# AM-Crystal-RX.net
KiCad netlist of a schematic drawn in EAGLE
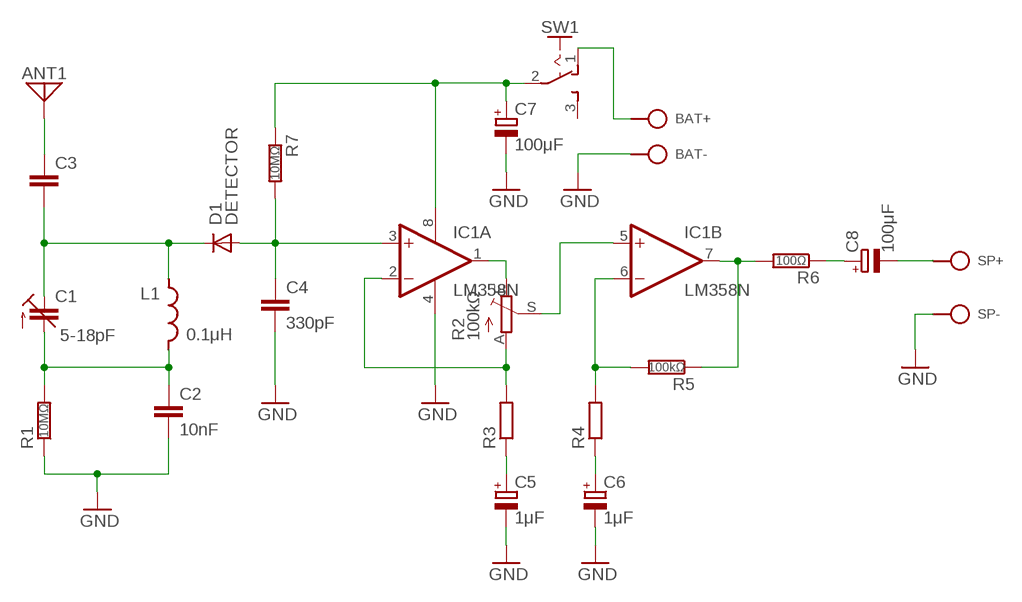
[diagram p0: schematic, sheet 1]

(export (version "E")
  (design (tool "Eeschema 10.0.6"))
  (components
    (comp (ref "ANT1")
      (value "ANT")
      (footprint "eagle-import:SPAD")
      (libsource (lib "eagle-import") (part "ANT"))
    )
    (comp (ref "BAT+")
      (value "BAT+")
      (footprint "eagle-import:SPAD")
      (libsource (lib "eagle-import") (part "SPAD"))
    )
    (comp (ref "BAT-")
      (value "BAT-")
      (footprint "eagle-import:SPAD")
      (libsource (lib "eagle-import") (part "SPAD"))
    )
    (comp (ref "C1")
      (value "5-18pF")
      (footprint "eagle-import:TRIM-2222-808")
      (libsource (lib "eagle-import") (part "C-TR-PH201272222-808-2PIN"))
    )
    (comp (ref "C2")
      (value "10nF")
      (footprint "eagle-import:C050-025X075")
      (libsource (lib "eagle-import") (part "C050-025X075"))
    )
    (comp (ref "C3")
      (value "C025-015X024")
      (footprint "eagle-import:C025-015X024")
      (libsource (lib "eagle-import") (part "C025-015X024"))
    )
    (comp (ref "C4")
      (value "330pF")
      (footprint "eagle-import:C050-024X044")
      (libsource (lib "eagle-import") (part "C050-024X044"))
    )
    (comp (ref "C5")
      (value "1μF")
      (footprint "eagle-import:E2,5-3")
      (libsource (lib "eagle-import") (part "CPOLE2,5-3"))
    )
    (comp (ref "C6")
      (value "1μF")
      (footprint "eagle-import:E2,5-3")
      (libsource (lib "eagle-import") (part "CPOLE2,5-3"))
    )
    (comp (ref "C7")
      (value "100μF")
      (footprint "eagle-import:E2,5-5")
      (libsource (lib "eagle-import") (part "CPOLE2.5-5"))
    )
    (comp (ref "C8")
      (value "100μF")
      (footprint "eagle-import:E2,5-5")
      (libsource (lib "eagle-import") (part "CPOLE2.5-5"))
    )
    (comp (ref "D1")
      (value "DETECTOR")
      (footprint "eagle-import:DO34-10")
      (libsource (lib "eagle-import") (part "1N414834-10"))
    )
    (comp (ref "IC1")
      (value "LM358N")
      (footprint "eagle-import:DIL08")
      (libsource (lib "eagle-import") (part "LM358N"))
    )
    (comp (ref "L1")
      (value "0.1μH")
      (footprint "eagle-import:L-04_10")
      (libsource (lib "eagle-import") (part "L-SHORT04/10"))
    )
    (comp (ref "R1")
      (value "10MΩ")
      (footprint "eagle-import:0202_7-V")
      (libsource (lib "eagle-import") (part "R0202/7-V"))
    )
    (comp (ref "R2")
      (value "100kΩ")
      (footprint "eagle-import:B64Y")
      (libsource (lib "eagle-import") (part "TRIM_EU-B64Y"))
    )
    (comp (ref "R3")
      (value "R0202/7")
      (footprint "eagle-import:0202_7")
      (libsource (lib "eagle-import") (part "R0202/7"))
    )
    (comp (ref "R4")
      (value "R0202/7")
      (footprint "eagle-import:0202_7")
      (libsource (lib "eagle-import") (part "R0202/7"))
    )
    (comp (ref "R5")
      (value "100kΩ")
      (footprint "eagle-import:0202_7")
      (libsource (lib "eagle-import") (part "R0202/7"))
    )
    (comp (ref "R6")
      (value "100Ω")
      (footprint "eagle-import:0202_7")
      (libsource (lib "eagle-import") (part "R0202/7"))
    )
    (comp (ref "R7")
      (value "10MΩ")
      (footprint "eagle-import:0202_7")
      (libsource (lib "eagle-import") (part "R0202/7"))
    )
    (comp (ref "SP+")
      (value "SPKR+")
      (footprint "eagle-import:SPAD")
      (libsource (lib "eagle-import") (part "SPAD"))
    )
    (comp (ref "SP-")
      (value "SPKR-")
      (footprint "eagle-import:SPAD")
      (libsource (lib "eagle-import") (part "SPAD"))
    )
    (comp (ref "SW1")
      (value "SL-SW-1P-2T-H")
      (footprint "eagle-import:SLSW-1P2T-H")
      (libsource (lib "eagle-import") (part "SL-SW-1P-2T-H"))
    )
  )
  (nets
    (net (code "1") (name "GND") (class "Default")
      (node (ref "BAT-") (pin "1") (pinfunction "P$1_1") (pintype "bidirectional"))
      (node (ref "C2") (pin "2") (pinfunction "2_2") (pintype "passive"))
      (node (ref "C4") (pin "2") (pinfunction "2_2") (pintype "passive"))
      (node (ref "C5") (pin "-") (pinfunction "-_-") (pintype "passive"))
      (node (ref "C6") (pin "-") (pinfunction "-_-") (pintype "passive"))
      (node (ref "C7") (pin "-") (pinfunction "-_-") (pintype "passive"))
      (node (ref "IC1") (pin "4") (pinfunction "V-_4") (pintype "power_in"))
      (node (ref "R1") (pin "1") (pinfunction "1_1") (pintype "passive"))
      (node (ref "SP-") (pin "1") (pinfunction "P$1_1") (pintype "bidirectional"))
    )
    (net (code "2") (name "Net-(ANT1-Pad1)") (class "Default")
      (node (ref "ANT1") (pin "1") (pinfunction "1_1") (pintype "output"))
      (node (ref "C3") (pin "1") (pinfunction "1_1") (pintype "passive"))
    )
    (net (code "3") (name "Net-(BAT+-P$1)") (class "Default")
      (node (ref "BAT+") (pin "1") (pinfunction "P$1_1") (pintype "bidirectional"))
      (node (ref "SW1") (pin "1") (pinfunction "O_1") (pintype "passive"))
    )
    (net (code "4") (name "Net-(C1-A)") (class "Default")
      (node (ref "C1") (pin "1") (pinfunction "A_1") (pintype "passive"))
      (node (ref "C3") (pin "2") (pinfunction "2_2") (pintype "passive"))
      (node (ref "D1") (pin "C") (pinfunction "C_C") (pintype "passive"))
      (node (ref "L1") (pin "1") (pinfunction "1_1") (pintype "passive"))
    )
    (net (code "5") (name "Net-(C1-E)") (class "Default")
      (node (ref "C1") (pin "2") (pinfunction "E_2") (pintype "passive"))
      (node (ref "C2") (pin "1") (pinfunction "1_1") (pintype "passive"))
      (node (ref "L1") (pin "2") (pinfunction "2_2") (pintype "passive"))
      (node (ref "R1") (pin "2") (pinfunction "2_2") (pintype "passive"))
    )
    (net (code "6") (name "Net-(C5-Pad+)") (class "Default")
      (node (ref "C5") (pin "+") (pinfunction "+_+") (pintype "passive"))
      (node (ref "R3") (pin "1") (pinfunction "1_1") (pintype "passive"))
    )
    (net (code "7") (name "Net-(C6-Pad+)") (class "Default")
      (node (ref "C6") (pin "+") (pinfunction "+_+") (pintype "passive"))
      (node (ref "R4") (pin "1") (pinfunction "1_1") (pintype "passive"))
    )
    (net (code "8") (name "Net-(C8-Pad+)") (class "Default")
      (node (ref "C8") (pin "+") (pinfunction "+_+") (pintype "passive"))
      (node (ref "R6") (pin "1") (pinfunction "1_1") (pintype "passive"))
    )
    (net (code "9") (name "Net-(IC1A-+IN)") (class "Default")
      (node (ref "C4") (pin "1") (pinfunction "1_1") (pintype "passive"))
      (node (ref "D1") (pin "A") (pinfunction "A_A") (pintype "passive"))
      (node (ref "IC1") (pin "3") (pinfunction "+IN_3") (pintype "input"))
      (node (ref "R7") (pin "2") (pinfunction "2_2") (pintype "passive"))
    )
    (net (code "10") (name "Net-(IC1A--IN)") (class "Default")
      (node (ref "IC1") (pin "2") (pinfunction "-IN_2") (pintype "input"))
      (node (ref "R2") (pin "A") (pinfunction "A_A") (pintype "passive"))
      (node (ref "R3") (pin "2") (pinfunction "2_2") (pintype "passive"))
    )
    (net (code "11") (name "Net-(IC1A-OUT)") (class "Default")
      (node (ref "IC1") (pin "1") (pinfunction "OUT_1") (pintype "output"))
      (node (ref "R2") (pin "E") (pinfunction "E_E") (pintype "passive"))
    )
    (net (code "12") (name "Net-(IC1B-+IN)") (class "Default")
      (node (ref "IC1") (pin "5") (pinfunction "+IN_5") (pintype "input"))
      (node (ref "R2") (pin "S") (pinfunction "S_S") (pintype "passive"))
    )
    (net (code "13") (name "Net-(IC1B--IN)") (class "Default")
      (node (ref "IC1") (pin "6") (pinfunction "-IN_6") (pintype "input"))
      (node (ref "R4") (pin "2") (pinfunction "2_2") (pintype "passive"))
      (node (ref "R5") (pin "2") (pinfunction "2_2") (pintype "passive"))
    )
    (net (code "14") (name "Net-(IC1B-OUT)") (class "Default")
      (node (ref "IC1") (pin "7") (pinfunction "OUT_7") (pintype "output"))
      (node (ref "R5") (pin "1") (pinfunction "1_1") (pintype "passive"))
      (node (ref "R6") (pin "2") (pinfunction "2_2") (pintype "passive"))
    )
    (net (code "15") (name "Net-(IC1C-V+)") (class "Default")
      (node (ref "C7") (pin "+") (pinfunction "+_+") (pintype "passive"))
      (node (ref "IC1") (pin "8") (pinfunction "V+_8") (pintype "power_in"))
      (node (ref "R7") (pin "1") (pinfunction "1_1") (pintype "passive"))
      (node (ref "SW1") (pin "2") (pinfunction "P_2") (pintype "passive"))
    )
    (net (code "16") (name "Net-(SP+-P$1)") (class "Default")
      (node (ref "C8") (pin "-") (pinfunction "-_-") (pintype "passive"))
      (node (ref "SP+") (pin "1") (pinfunction "P$1_1") (pintype "bidirectional"))
    )
    (net (code "17") (name "unconnected-(SW1-S-Pad3)") (class "Default")
      (node (ref "SW1") (pin "3") (pinfunction "S_3") (pintype "passive"))
    )
  )
)
